# Bluetooth_fm_transmitter.net
KiCad netlist of a schematic drawn in EAGLE
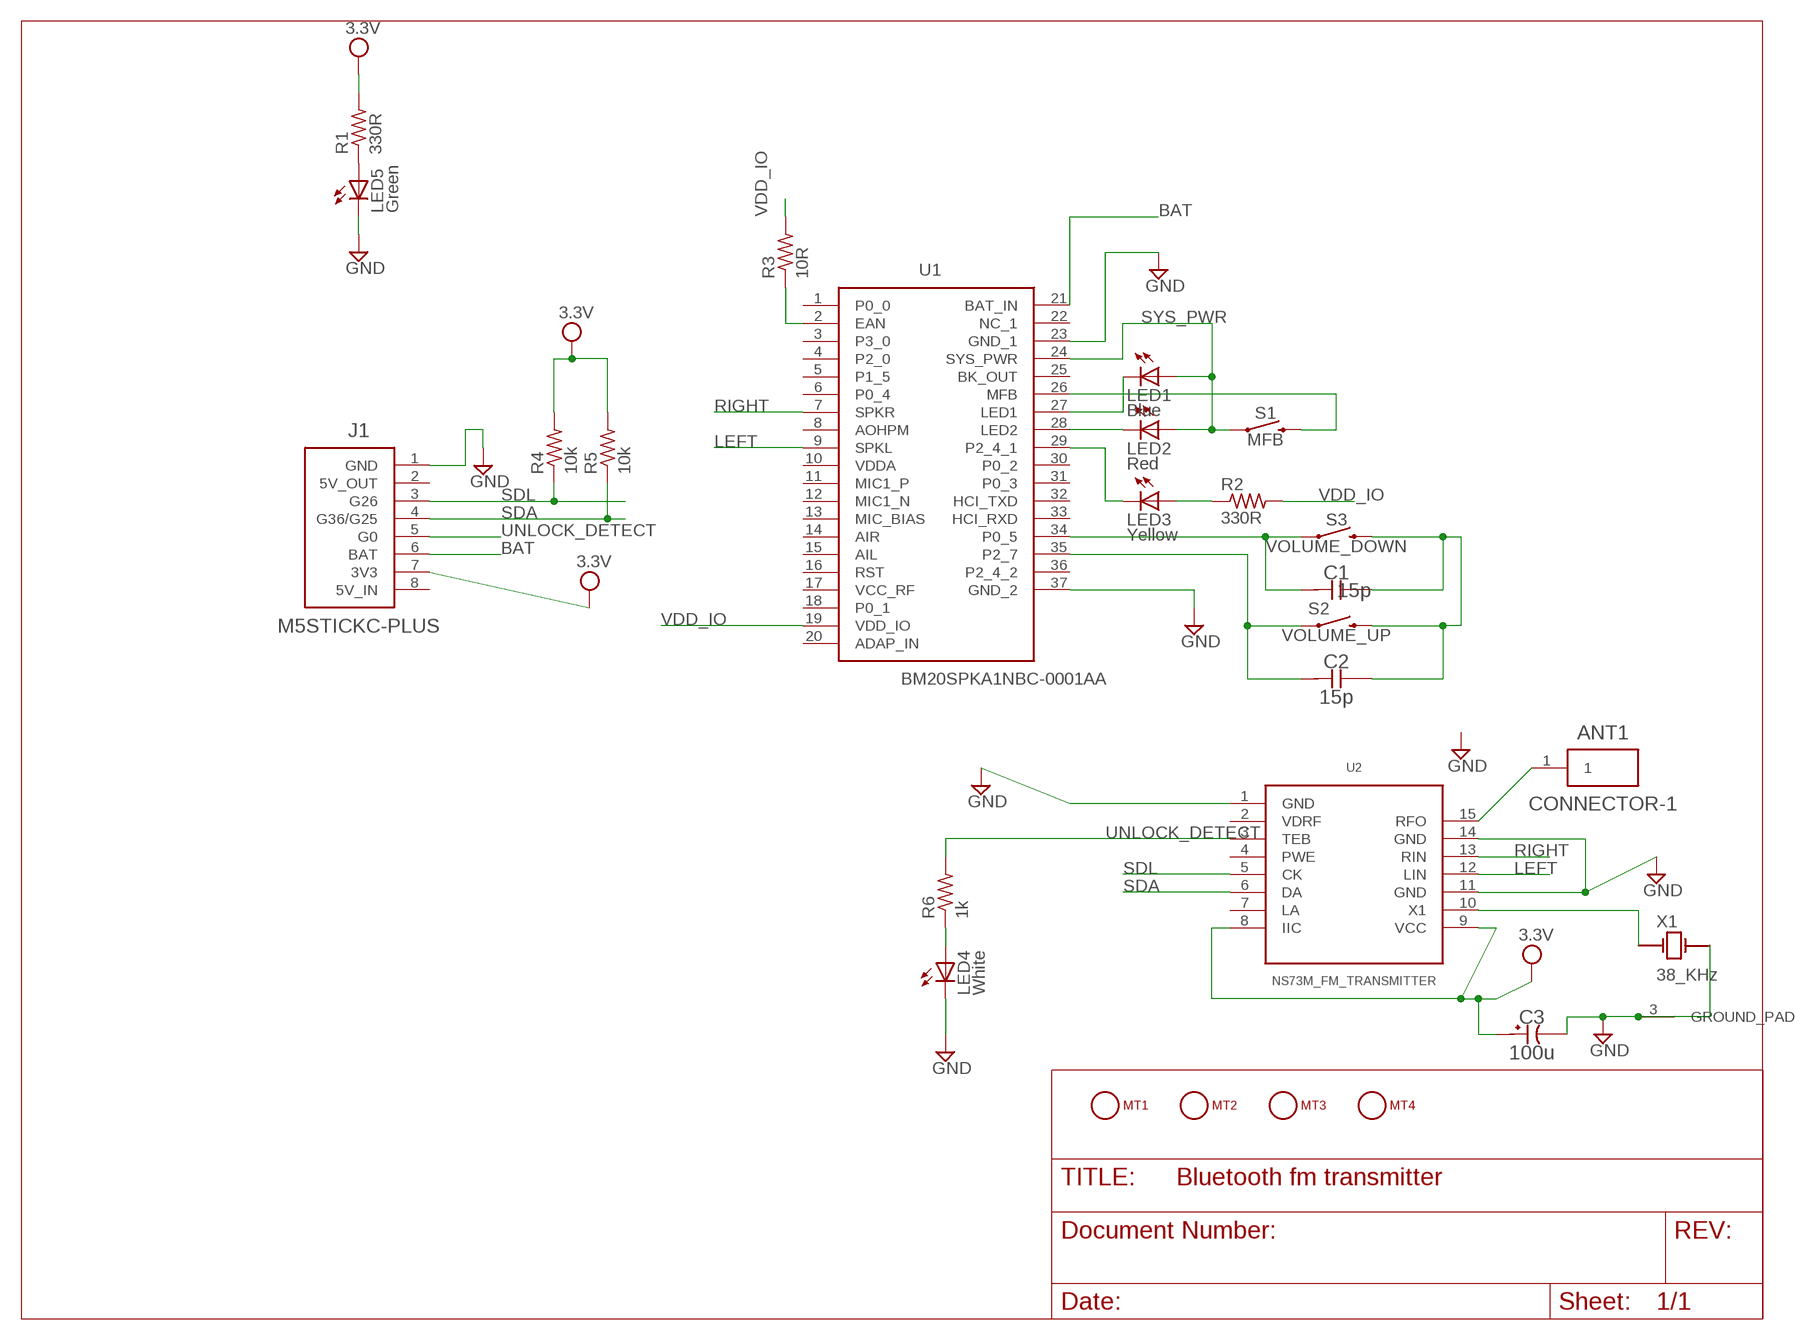
[diagram p0: schematic, sheet 1]

(export (version "E")
  (design (tool "Eeschema 10.0.6"))
  (components
    (comp (ref "ANT1")
      (value "CONNECTOR-1")
      (footprint "eagle-import:ESQ-101-XX-X-S")
      (libsource (lib "eagle-import") (part "CONNECTOR-1"))
    )
    (comp (ref "C1")
      (value "15p")
      (footprint "eagle-import:CAPC1608X90L30N")
      (libsource (lib "eagle-import") (part "CAPACITOR-0603"))
    )
    (comp (ref "C2")
      (value "15p")
      (footprint "eagle-import:CAPC1608X90L30N")
      (libsource (lib "eagle-import") (part "CAPACITOR-0603"))
    )
    (comp (ref "C3")
      (value "100u")
      (footprint "eagle-import:CAPACITOR_TH_8MM_3.5MM_0.6MM")
      (libsource (lib "eagle-import") (part "CAPACITOR_POLARIZED"))
    )
    (comp (ref "J1")
      (value "M5STICKC-PLUS")
      (footprint "eagle-import:M5STICKC-PLUS")
      (libsource (lib "eagle-import") (part "M5STICKC-PLUS"))
    )
    (comp (ref "LED1")
      (value "Blue")
      (footprint "eagle-import:LED5MM")
      (libsource (lib "eagle-import") (part "LED5MM"))
    )
    (comp (ref "LED2")
      (value "Red")
      (footprint "eagle-import:LED5MM")
      (libsource (lib "eagle-import") (part "LED5MM"))
    )
    (comp (ref "LED3")
      (value "Yellow")
      (footprint "eagle-import:LED5MM")
      (libsource (lib "eagle-import") (part "LED5MM"))
    )
    (comp (ref "LED4")
      (value "White")
      (footprint "eagle-import:LED5MM")
      (libsource (lib "eagle-import") (part "LED5MM"))
    )
    (comp (ref "LED5")
      (value "Green")
      (footprint "eagle-import:LED5MM")
      (libsource (lib "eagle-import") (part "LED5MM"))
    )
    (comp (ref "MT1")
      (value "MOUNTING_HOLE-125_250_ROUND")
      (footprint "eagle-import:MT_125_250")
      (libsource (lib "eagle-import") (part "MOUNTING_HOLE-125_250_ROUND"))
    )
    (comp (ref "MT2")
      (value "MOUNTING_HOLE-125_250_ROUND")
      (footprint "eagle-import:MT_125_250")
      (libsource (lib "eagle-import") (part "MOUNTING_HOLE-125_250_ROUND"))
    )
    (comp (ref "MT3")
      (value "MOUNTING_HOLE-125_250_ROUND")
      (footprint "eagle-import:MT_125_250")
      (libsource (lib "eagle-import") (part "MOUNTING_HOLE-125_250_ROUND"))
    )
    (comp (ref "MT4")
      (value "MOUNTING_HOLE-125_250_ROUND")
      (footprint "eagle-import:MT_125_250")
      (libsource (lib "eagle-import") (part "MOUNTING_HOLE-125_250_ROUND"))
    )
    (comp (ref "R1")
      (value "330R")
      (footprint "eagle-import:V234_12")
      (libsource (lib "eagle-import") (part "R-US_V234/12"))
    )
    (comp (ref "R2")
      (value "330R")
      (footprint "eagle-import:V234_12")
      (libsource (lib "eagle-import") (part "R-US_V234/12"))
    )
    (comp (ref "R3")
      (value "10R")
      (footprint "eagle-import:V234_12")
      (libsource (lib "eagle-import") (part "R-US_V234/12"))
    )
    (comp (ref "R4")
      (value "10k")
      (footprint "eagle-import:V234_12")
      (libsource (lib "eagle-import") (part "R-US_V234/12"))
    )
    (comp (ref "R5")
      (value "10k")
      (footprint "eagle-import:V234_12")
      (libsource (lib "eagle-import") (part "R-US_V234/12"))
    )
    (comp (ref "R6")
      (value "1k")
      (footprint "eagle-import:V234_12")
      (libsource (lib "eagle-import") (part "R-US_V234/12"))
    )
    (comp (ref "S1")
      (value "MFB")
      (footprint "eagle-import:TACTILE_SWITCH_PTH_6.0MM")
      (libsource (lib "eagle-import") (part "MOMENTARY-SWITCH-SPST-PTH-6.0MM"))
    )
    (comp (ref "S2")
      (value "VOLUME_UP")
      (footprint "eagle-import:TACTILE_SWITCH_PTH_6.0MM")
      (libsource (lib "eagle-import") (part "MOMENTARY-SWITCH-SPST-PTH-6.0MM"))
    )
    (comp (ref "S3")
      (value "VOLUME_DOWN")
      (footprint "eagle-import:TACTILE_SWITCH_PTH_6.0MM")
      (libsource (lib "eagle-import") (part "MOMENTARY-SWITCH-SPST-PTH-6.0MM"))
    )
    (comp (ref "U1")
      (value "BM20SPKA1NBC-0001AA")
      (footprint "eagle-import:BM20SPKA1NBC0001AA")
      (fields (field (name "MOUSER_PART_NUMBER") "579-SPKA1NBC-0001AA"))
      (libsource (lib "eagle-import") (part "BM20SPKA1NBC-0001AA"))
    )
    (comp (ref "U2")
      (value "NS73M_FM_TRANSMITTER")
      (footprint "eagle-import:NS73M")
      (libsource (lib "eagle-import") (part "NS73M_FM_TRANSMITTER"))
    )
    (comp (ref "X1")
      (value "38_KHz")
      (footprint "eagle-import:XTAL-WITH-GROUND-PAD")
      (libsource (lib "eagle-import") (part "XTAL_38_KHZ_GROUND_PAD"))
    )
  )
  (nets
    (net (code "1") (name "/BAT") (class "Default")
      (node (ref "J1") (pin "6") (pinfunction "BAT_6") (pintype "bidirectional"))
      (node (ref "U1") (pin "21") (pinfunction "BAT_IN_21") (pintype "bidirectional"))
    )
    (net (code "2") (name "/LEFT") (class "Default")
      (node (ref "U1") (pin "9") (pinfunction "SPKL_9") (pintype "bidirectional"))
      (node (ref "U2") (pin "12") (pinfunction "LIN_12") (pintype "bidirectional"))
    )
    (net (code "3") (name "/RIGHT") (class "Default")
      (node (ref "U1") (pin "7") (pinfunction "SPKR_7") (pintype "bidirectional"))
      (node (ref "U2") (pin "13") (pinfunction "RIN_13") (pintype "bidirectional"))
    )
    (net (code "4") (name "/SDA") (class "Default")
      (node (ref "J1") (pin "4") (pinfunction "G36/G25_4") (pintype "bidirectional"))
      (node (ref "R5") (pin "1") (pinfunction "1_1") (pintype "passive"))
      (node (ref "U2") (pin "6") (pinfunction "DA_6") (pintype "bidirectional"))
    )
    (net (code "5") (name "/SDL") (class "Default")
      (node (ref "J1") (pin "3") (pinfunction "G26_3") (pintype "bidirectional"))
      (node (ref "R4") (pin "1") (pinfunction "1_1") (pintype "passive"))
      (node (ref "U2") (pin "5") (pinfunction "CK_5") (pintype "bidirectional"))
    )
    (net (code "6") (name "/SYS_PWR") (class "Default")
      (node (ref "LED1") (pin "A") (pinfunction "A_A") (pintype "passive"))
      (node (ref "LED2") (pin "A") (pinfunction "A_A") (pintype "passive"))
      (node (ref "S1") (pin "1") (pinfunction "1_1") (pintype "passive"))
      (node (ref "U1") (pin "24") (pinfunction "SYS_PWR_24") (pintype "bidirectional"))
    )
    (net (code "7") (name "/UNLOCK_DETECT") (class "Default")
      (node (ref "J1") (pin "5") (pinfunction "G0_5") (pintype "bidirectional"))
      (node (ref "R6") (pin "2") (pinfunction "2_2") (pintype "passive"))
      (node (ref "U2") (pin "3") (pinfunction "TEB_3") (pintype "bidirectional"))
    )
    (net (code "8") (name "/VDD_IO") (class "Default")
      (node (ref "R2") (pin "2") (pinfunction "2_2") (pintype "passive"))
      (node (ref "R3") (pin "2") (pinfunction "2_2") (pintype "passive"))
      (node (ref "U1") (pin "19") (pinfunction "VDD_IO_19") (pintype "bidirectional"))
    )
    (net (code "9") (name "3.3V") (class "Default")
      (node (ref "C3") (pin "POSITIVE") (pinfunction "1_POSITIVE") (pintype "bidirectional"))
      (node (ref "J1") (pin "7") (pinfunction "3V3_7") (pintype "bidirectional"))
      (node (ref "R1") (pin "2") (pinfunction "2_2") (pintype "passive"))
      (node (ref "R4") (pin "2") (pinfunction "2_2") (pintype "passive"))
      (node (ref "R5") (pin "2") (pinfunction "2_2") (pintype "passive"))
      (node (ref "U2") (pin "8") (pinfunction "IIC_8") (pintype "bidirectional"))
      (node (ref "U2") (pin "9") (pinfunction "VCC_9") (pintype "bidirectional"))
    )
    (net (code "10") (name "GND") (class "Default")
      (node (ref "C3") (pin "NEGATIVE") (pinfunction "2_NEGATIVE") (pintype "bidirectional"))
      (node (ref "J1") (pin "1") (pinfunction "GND_1") (pintype "bidirectional"))
      (node (ref "LED4") (pin "K") (pinfunction "C_K") (pintype "passive"))
      (node (ref "LED5") (pin "K") (pinfunction "C_K") (pintype "passive"))
      (node (ref "U1") (pin "23") (pinfunction "GND_1_23") (pintype "bidirectional"))
      (node (ref "U1") (pin "37") (pinfunction "GND_2_37") (pintype "bidirectional"))
      (node (ref "U2") (pin "1") (pinfunction "GND_1") (pintype "bidirectional"))
      (node (ref "U2") (pin "11") (pinfunction "GND_11") (pintype "bidirectional"))
      (node (ref "U2") (pin "14") (pinfunction "GND_14") (pintype "bidirectional"))
      (node (ref "X1") (pin "2") (pinfunction "2_2") (pintype "passive"))
      (node (ref "X1") (pin "3") (pinfunction "GROUND_PAD_3") (pintype "bidirectional"))
    )
    (net (code "11") (name "Net-(LED1-C)") (class "Default")
      (node (ref "LED1") (pin "K") (pinfunction "C_K") (pintype "passive"))
      (node (ref "U1") (pin "27") (pinfunction "LED1_27") (pintype "bidirectional"))
    )
    (net (code "12") (name "Net-(LED2-C)") (class "Default")
      (node (ref "LED2") (pin "K") (pinfunction "C_K") (pintype "passive"))
      (node (ref "U1") (pin "28") (pinfunction "LED2_28") (pintype "bidirectional"))
    )
    (net (code "13") (name "Net-(LED3-C)") (class "Default")
      (node (ref "LED3") (pin "K") (pinfunction "C_K") (pintype "passive"))
      (node (ref "U1") (pin "29") (pinfunction "P2_4_1_29") (pintype "bidirectional"))
    )
    (net (code "14") (name "Net-(LED3-PadA)") (class "Default")
      (node (ref "LED3") (pin "A") (pinfunction "A_A") (pintype "passive"))
      (node (ref "R2") (pin "1") (pinfunction "1_1") (pintype "passive"))
    )
    (net (code "15") (name "Net-(LED4-PadA)") (class "Default")
      (node (ref "LED4") (pin "A") (pinfunction "A_A") (pintype "passive"))
      (node (ref "R6") (pin "1") (pinfunction "1_1") (pintype "passive"))
    )
    (net (code "16") (name "Net-(LED5-PadA)") (class "Default")
      (node (ref "LED5") (pin "A") (pinfunction "A_A") (pintype "passive"))
      (node (ref "R1") (pin "1") (pinfunction "1_1") (pintype "passive"))
    )
    (net (code "17") (name "Net-(S1-2)") (class "Default")
      (node (ref "S1") (pin "3") (pinfunction "2_3") (pintype "passive"))
      (node (ref "U1") (pin "26") (pinfunction "MFB_26") (pintype "bidirectional"))
    )
    (net (code "18") (name "Net-(S2-2)") (class "Default")
      (node (ref "C1") (pin "2") (pinfunction "2_2") (pintype "bidirectional"))
      (node (ref "C2") (pin "2") (pinfunction "2_2") (pintype "bidirectional"))
      (node (ref "S2") (pin "3") (pinfunction "2_3") (pintype "passive"))
      (node (ref "S3") (pin "3") (pinfunction "2_3") (pintype "passive"))
    )
    (net (code "19") (name "Net-(U1-EAN)") (class "Default")
      (node (ref "R3") (pin "1") (pinfunction "1_1") (pintype "passive"))
      (node (ref "U1") (pin "2") (pinfunction "EAN_2") (pintype "bidirectional"))
    )
    (net (code "20") (name "Net-(U1-P0_5)") (class "Default")
      (node (ref "C1") (pin "1") (pinfunction "1_1") (pintype "bidirectional"))
      (node (ref "S3") (pin "1") (pinfunction "1_1") (pintype "passive"))
      (node (ref "U1") (pin "34") (pinfunction "P0_5_34") (pintype "bidirectional"))
    )
    (net (code "21") (name "Net-(U1-P2_7)") (class "Default")
      (node (ref "C2") (pin "1") (pinfunction "1_1") (pintype "bidirectional"))
      (node (ref "S2") (pin "1") (pinfunction "1_1") (pintype "passive"))
      (node (ref "U1") (pin "35") (pinfunction "P2_7_35") (pintype "bidirectional"))
    )
    (net (code "22") (name "Net-(U2-RFO)") (class "Default")
      (node (ref "ANT1") (pin "1") (pinfunction "1_1") (pintype "bidirectional"))
      (node (ref "U2") (pin "15") (pinfunction "RFO_15") (pintype "bidirectional"))
    )
    (net (code "23") (name "Net-(U2-X1)") (class "Default")
      (node (ref "U2") (pin "10") (pinfunction "X1_10") (pintype "bidirectional"))
      (node (ref "X1") (pin "1") (pinfunction "1_1") (pintype "passive"))
    )
    (net (code "24") (name "unconnected-(J1-5V_IN-Pad8)") (class "Default")
      (node (ref "J1") (pin "8") (pinfunction "5V_IN_8") (pintype "bidirectional"))
    )
    (net (code "25") (name "unconnected-(J1-5V_OUT-Pad2)") (class "Default")
      (node (ref "J1") (pin "2") (pinfunction "5V_OUT_2") (pintype "bidirectional"))
    )
    (net (code "26") (name "unconnected-(MT1-P$1-Pad1)") (class "Default")
      (node (ref "MT1") (pin "1") (pinfunction "P$1_1") (pintype "bidirectional"))
    )
    (net (code "27") (name "unconnected-(MT2-P$1-Pad1)") (class "Default")
      (node (ref "MT2") (pin "1") (pinfunction "P$1_1") (pintype "bidirectional"))
    )
    (net (code "28") (name "unconnected-(MT3-P$1-Pad1)") (class "Default")
      (node (ref "MT3") (pin "1") (pinfunction "P$1_1") (pintype "bidirectional"))
    )
    (net (code "29") (name "unconnected-(MT4-P$1-Pad1)") (class "Default")
      (node (ref "MT4") (pin "1") (pinfunction "P$1_1") (pintype "bidirectional"))
    )
    (net (code "30") (name "unconnected-(U1-ADAP_IN-Pad20)") (class "Default")
      (node (ref "U1") (pin "20") (pinfunction "ADAP_IN_20") (pintype "bidirectional"))
    )
    (net (code "31") (name "unconnected-(U1-AIL-Pad15)") (class "Default")
      (node (ref "U1") (pin "15") (pinfunction "AIL_15") (pintype "bidirectional"))
    )
    (net (code "32") (name "unconnected-(U1-AIR-Pad14)") (class "Default")
      (node (ref "U1") (pin "14") (pinfunction "AIR_14") (pintype "bidirectional"))
    )
    (net (code "33") (name "unconnected-(U1-AOHPM-Pad8)") (class "Default")
      (node (ref "U1") (pin "8") (pinfunction "AOHPM_8") (pintype "bidirectional"))
    )
    (net (code "34") (name "unconnected-(U1-BK_OUT-Pad25)") (class "Default")
      (node (ref "U1") (pin "25") (pinfunction "BK_OUT_25") (pintype "bidirectional"))
    )
    (net (code "35") (name "unconnected-(U1-HCI_RXD-Pad33)") (class "Default")
      (node (ref "U1") (pin "33") (pinfunction "HCI_RXD_33") (pintype "bidirectional"))
    )
    (net (code "36") (name "unconnected-(U1-HCI_TXD-Pad32)") (class "Default")
      (node (ref "U1") (pin "32") (pinfunction "HCI_TXD_32") (pintype "bidirectional"))
    )
    (net (code "37") (name "unconnected-(U1-MIC1_N-Pad12)") (class "Default")
      (node (ref "U1") (pin "12") (pinfunction "MIC1_N_12") (pintype "bidirectional"))
    )
    (net (code "38") (name "unconnected-(U1-MIC1_P-Pad11)") (class "Default")
      (node (ref "U1") (pin "11") (pinfunction "MIC1_P_11") (pintype "bidirectional"))
    )
    (net (code "39") (name "unconnected-(U1-MIC_BIAS-Pad13)") (class "Default")
      (node (ref "U1") (pin "13") (pinfunction "MIC_BIAS_13") (pintype "bidirectional"))
    )
    (net (code "40") (name "unconnected-(U1-NC_1-Pad22)") (class "Default")
      (node (ref "U1") (pin "22") (pinfunction "NC_1_22") (pintype "bidirectional"))
    )
    (net (code "41") (name "unconnected-(U1-P0_0-Pad1)") (class "Default")
      (node (ref "U1") (pin "1") (pinfunction "P0_0_1") (pintype "bidirectional"))
    )
    (net (code "42") (name "unconnected-(U1-P0_1-Pad18)") (class "Default")
      (node (ref "U1") (pin "18") (pinfunction "P0_1_18") (pintype "bidirectional"))
    )
    (net (code "43") (name "unconnected-(U1-P0_2-Pad30)") (class "Default")
      (node (ref "U1") (pin "30") (pinfunction "P0_2_30") (pintype "bidirectional"))
    )
    (net (code "44") (name "unconnected-(U1-P0_3-Pad31)") (class "Default")
      (node (ref "U1") (pin "31") (pinfunction "P0_3_31") (pintype "bidirectional"))
    )
    (net (code "45") (name "unconnected-(U1-P0_4-Pad6)") (class "Default")
      (node (ref "U1") (pin "6") (pinfunction "P0_4_6") (pintype "bidirectional"))
    )
    (net (code "46") (name "unconnected-(U1-P1_5-Pad5)") (class "Default")
      (node (ref "U1") (pin "5") (pinfunction "P1_5_5") (pintype "bidirectional"))
    )
    (net (code "47") (name "unconnected-(U1-P2_0-Pad4)") (class "Default")
      (node (ref "U1") (pin "4") (pinfunction "P2_0_4") (pintype "bidirectional"))
    )
    (net (code "48") (name "unconnected-(U1-P2_4_2-Pad36)") (class "Default")
      (node (ref "U1") (pin "36") (pinfunction "P2_4_2_36") (pintype "bidirectional"))
    )
    (net (code "49") (name "unconnected-(U1-P3_0-Pad3)") (class "Default")
      (node (ref "U1") (pin "3") (pinfunction "P3_0_3") (pintype "bidirectional"))
    )
    (net (code "50") (name "unconnected-(U1-RST-Pad16)") (class "Default")
      (node (ref "U1") (pin "16") (pinfunction "RST_16") (pintype "bidirectional"))
    )
    (net (code "51") (name "unconnected-(U1-VCC_RF-Pad17)") (class "Default")
      (node (ref "U1") (pin "17") (pinfunction "VCC_RF_17") (pintype "bidirectional"))
    )
    (net (code "52") (name "unconnected-(U1-VDDA-Pad10)") (class "Default")
      (node (ref "U1") (pin "10") (pinfunction "VDDA_10") (pintype "bidirectional"))
    )
    (net (code "53") (name "unconnected-(U2-LA-Pad7)") (class "Default")
      (node (ref "U2") (pin "7") (pinfunction "LA_7") (pintype "bidirectional"))
    )
    (net (code "54") (name "unconnected-(U2-PWE-Pad4)") (class "Default")
      (node (ref "U2") (pin "4") (pinfunction "PWE_4") (pintype "bidirectional"))
    )
    (net (code "55") (name "unconnected-(U2-VDRF-Pad2)") (class "Default")
      (node (ref "U2") (pin "2") (pinfunction "VDRF_2") (pintype "bidirectional"))
    )
  )
)
